# FredT232H_Board.net
KiCad netlist of a schematic drawn in EAGLE
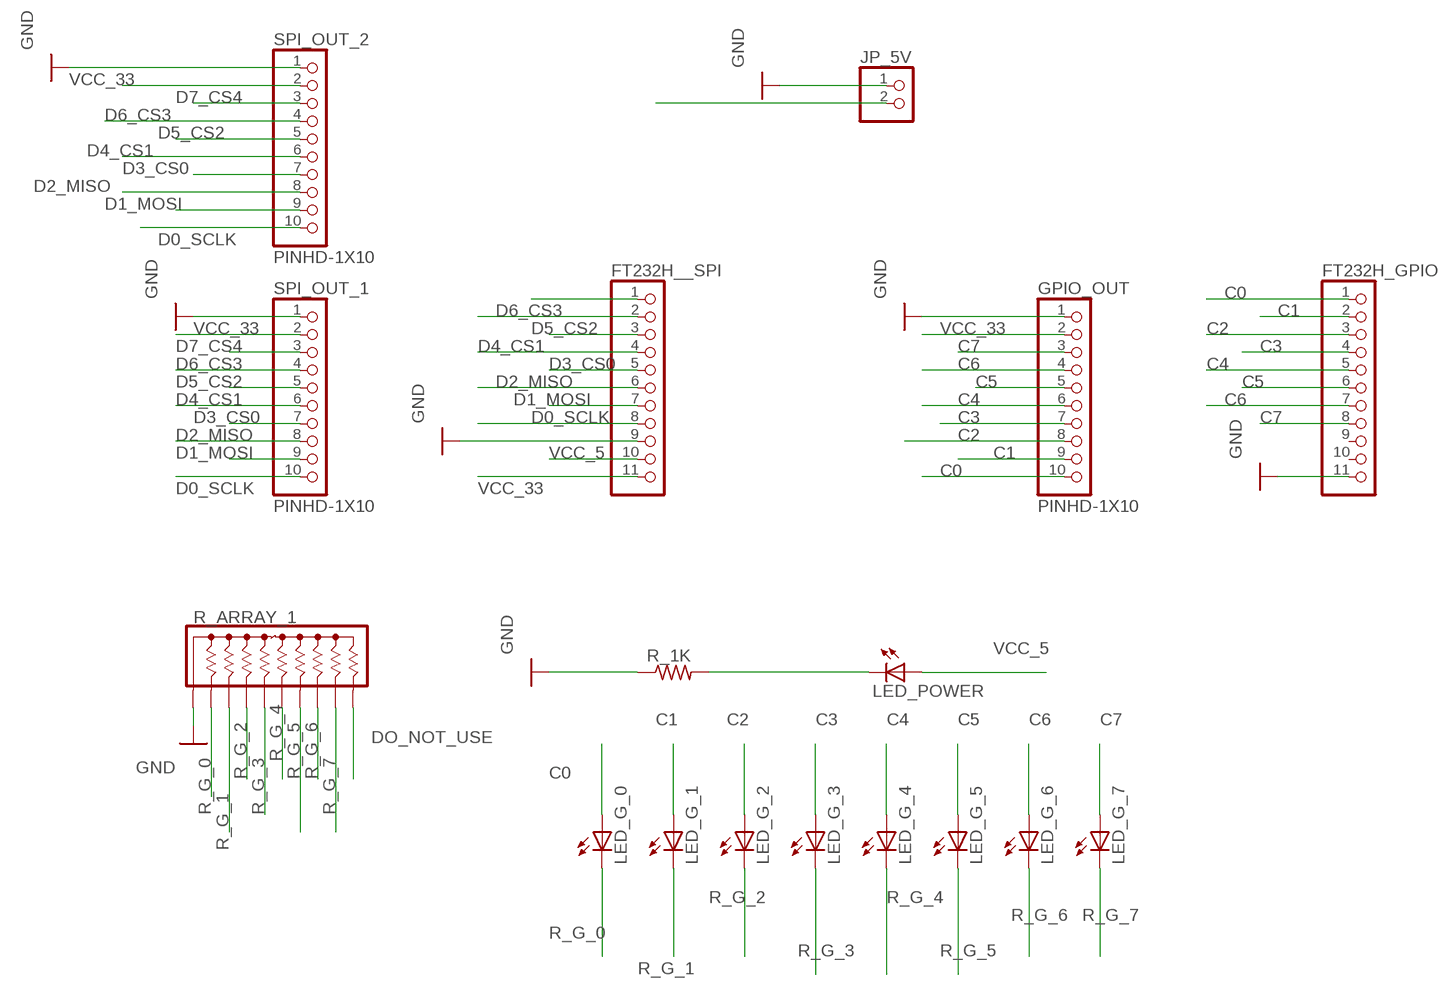
[diagram p0: schematic, sheet 1]

(export (version "E")
  (design (tool "Eeschema 10.0.6"))
  (components
    (comp (ref "FT232H_GPIO")
      (value "PINHD-1X11")
      (footprint "eagle-import:1X11")
      (libsource (lib "eagle-import") (part "PINHD-1X11"))
    )
    (comp (ref "FT232H__SPI")
      (value "PINHD-1X11")
      (footprint "eagle-import:1X11")
      (libsource (lib "eagle-import") (part "PINHD-1X11"))
    )
    (comp (ref "GPIO_OUT")
      (value "PINHD-1X10")
      (footprint "eagle-import:1X10-BIG")
      (libsource (lib "eagle-import") (part "PINHD-1X10"))
    )
    (comp (ref "JP_5V")
      (value "PINHD-1X2")
      (footprint "eagle-import:1X02")
      (libsource (lib "eagle-import") (part "PINHD-1X2"))
    )
    (comp (ref "LED_G_0")
      (value "LEDSMT1206")
      (footprint "eagle-import:1206")
      (libsource (lib "eagle-import") (part "LEDSMT1206"))
    )
    (comp (ref "LED_G_1")
      (value "LEDSMT1206")
      (footprint "eagle-import:1206")
      (libsource (lib "eagle-import") (part "LEDSMT1206"))
    )
    (comp (ref "LED_G_2")
      (value "LEDSMT1206")
      (footprint "eagle-import:1206")
      (libsource (lib "eagle-import") (part "LEDSMT1206"))
    )
    (comp (ref "LED_G_3")
      (value "LEDSMT1206")
      (footprint "eagle-import:1206")
      (libsource (lib "eagle-import") (part "LEDSMT1206"))
    )
    (comp (ref "LED_G_4")
      (value "LEDSMT1206")
      (footprint "eagle-import:1206")
      (libsource (lib "eagle-import") (part "LEDSMT1206"))
    )
    (comp (ref "LED_G_5")
      (value "LEDSMT1206")
      (footprint "eagle-import:1206")
      (libsource (lib "eagle-import") (part "LEDSMT1206"))
    )
    (comp (ref "LED_G_6")
      (value "LEDSMT1206")
      (footprint "eagle-import:1206")
      (libsource (lib "eagle-import") (part "LEDSMT1206"))
    )
    (comp (ref "LED_G_7")
      (value "LEDSMT1206")
      (footprint "eagle-import:1206")
      (libsource (lib "eagle-import") (part "LEDSMT1206"))
    )
    (comp (ref "LED_POWER")
      (value "LEDSMT1206")
      (footprint "eagle-import:1206")
      (libsource (lib "eagle-import") (part "LEDSMT1206"))
    )
    (comp (ref "R_1K")
      (value "R-US_R1206")
      (footprint "eagle-import:R1206")
      (libsource (lib "eagle-import") (part "R-US_R1206"))
    )
    (comp (ref "R_ARRAY_1")
      (value "4610X")
      (footprint "eagle-import:SIP10")
      (libsource (lib "eagle-import") (part "4610X"))
    )
    (comp (ref "SPI_OUT_1")
      (value "PINHD-1X10")
      (footprint "eagle-import:1X10-BIG")
      (libsource (lib "eagle-import") (part "PINHD-1X10"))
    )
    (comp (ref "SPI_OUT_2")
      (value "PINHD-1X10")
      (footprint "eagle-import:1X10-BIG")
      (libsource (lib "eagle-import") (part "PINHD-1X10"))
    )
  )
  (nets
    (net (code "1") (name "/C0") (class "Default")
      (node (ref "FT232H_GPIO") (pin "1") (pinfunction "1_1") (pintype "passive"))
      (node (ref "GPIO_OUT") (pin "10") (pinfunction "10_10") (pintype "passive"))
      (node (ref "LED_G_0") (pin "A") (pinfunction "A_A") (pintype "passive"))
    )
    (net (code "2") (name "/C1") (class "Default")
      (node (ref "FT232H_GPIO") (pin "2") (pinfunction "2_2") (pintype "passive"))
      (node (ref "GPIO_OUT") (pin "9") (pinfunction "9_9") (pintype "passive"))
      (node (ref "LED_G_1") (pin "A") (pinfunction "A_A") (pintype "passive"))
    )
    (net (code "3") (name "/C2") (class "Default")
      (node (ref "FT232H_GPIO") (pin "3") (pinfunction "3_3") (pintype "passive"))
      (node (ref "GPIO_OUT") (pin "8") (pinfunction "8_8") (pintype "passive"))
      (node (ref "LED_G_2") (pin "A") (pinfunction "A_A") (pintype "passive"))
    )
    (net (code "4") (name "/C3") (class "Default")
      (node (ref "FT232H_GPIO") (pin "4") (pinfunction "4_4") (pintype "passive"))
      (node (ref "GPIO_OUT") (pin "7") (pinfunction "7_7") (pintype "passive"))
      (node (ref "LED_G_3") (pin "A") (pinfunction "A_A") (pintype "passive"))
    )
    (net (code "5") (name "/C4") (class "Default")
      (node (ref "FT232H_GPIO") (pin "5") (pinfunction "5_5") (pintype "passive"))
      (node (ref "GPIO_OUT") (pin "6") (pinfunction "6_6") (pintype "passive"))
      (node (ref "LED_G_4") (pin "A") (pinfunction "A_A") (pintype "passive"))
    )
    (net (code "6") (name "/C5") (class "Default")
      (node (ref "FT232H_GPIO") (pin "6") (pinfunction "6_6") (pintype "passive"))
      (node (ref "GPIO_OUT") (pin "5") (pinfunction "5_5") (pintype "passive"))
      (node (ref "LED_G_5") (pin "A") (pinfunction "A_A") (pintype "passive"))
    )
    (net (code "7") (name "/C6") (class "Default")
      (node (ref "FT232H_GPIO") (pin "7") (pinfunction "7_7") (pintype "passive"))
      (node (ref "GPIO_OUT") (pin "4") (pinfunction "4_4") (pintype "passive"))
      (node (ref "LED_G_6") (pin "A") (pinfunction "A_A") (pintype "passive"))
    )
    (net (code "8") (name "/C7") (class "Default")
      (node (ref "FT232H_GPIO") (pin "8") (pinfunction "8_8") (pintype "passive"))
      (node (ref "GPIO_OUT") (pin "3") (pinfunction "3_3") (pintype "passive"))
      (node (ref "LED_G_7") (pin "A") (pinfunction "A_A") (pintype "passive"))
    )
    (net (code "9") (name "/D0_SCLK") (class "Default")
      (node (ref "FT232H__SPI") (pin "8") (pinfunction "8_8") (pintype "passive"))
      (node (ref "SPI_OUT_1") (pin "10") (pinfunction "10_10") (pintype "passive"))
      (node (ref "SPI_OUT_2") (pin "10") (pinfunction "10_10") (pintype "passive"))
    )
    (net (code "10") (name "/D1_MOSI") (class "Default")
      (node (ref "FT232H__SPI") (pin "7") (pinfunction "7_7") (pintype "passive"))
      (node (ref "SPI_OUT_1") (pin "9") (pinfunction "9_9") (pintype "passive"))
      (node (ref "SPI_OUT_2") (pin "9") (pinfunction "9_9") (pintype "passive"))
    )
    (net (code "11") (name "/D2_MISO") (class "Default")
      (node (ref "FT232H__SPI") (pin "6") (pinfunction "6_6") (pintype "passive"))
      (node (ref "SPI_OUT_1") (pin "8") (pinfunction "8_8") (pintype "passive"))
      (node (ref "SPI_OUT_2") (pin "8") (pinfunction "8_8") (pintype "passive"))
    )
    (net (code "12") (name "/D3_CS0") (class "Default")
      (node (ref "FT232H__SPI") (pin "5") (pinfunction "5_5") (pintype "passive"))
      (node (ref "SPI_OUT_1") (pin "7") (pinfunction "7_7") (pintype "passive"))
      (node (ref "SPI_OUT_2") (pin "7") (pinfunction "7_7") (pintype "passive"))
    )
    (net (code "13") (name "/D4_CS1") (class "Default")
      (node (ref "FT232H__SPI") (pin "4") (pinfunction "4_4") (pintype "passive"))
      (node (ref "SPI_OUT_1") (pin "6") (pinfunction "6_6") (pintype "passive"))
      (node (ref "SPI_OUT_2") (pin "6") (pinfunction "6_6") (pintype "passive"))
    )
    (net (code "14") (name "/D5_CS2") (class "Default")
      (node (ref "FT232H__SPI") (pin "3") (pinfunction "3_3") (pintype "passive"))
      (node (ref "SPI_OUT_1") (pin "5") (pinfunction "5_5") (pintype "passive"))
      (node (ref "SPI_OUT_2") (pin "5") (pinfunction "5_5") (pintype "passive"))
    )
    (net (code "15") (name "/D6_CS3") (class "Default")
      (node (ref "FT232H__SPI") (pin "2") (pinfunction "2_2") (pintype "passive"))
      (node (ref "SPI_OUT_1") (pin "4") (pinfunction "4_4") (pintype "passive"))
      (node (ref "SPI_OUT_2") (pin "4") (pinfunction "4_4") (pintype "passive"))
    )
    (net (code "16") (name "/D7_CS4") (class "Default")
      (node (ref "FT232H__SPI") (pin "1") (pinfunction "1_1") (pintype "passive"))
      (node (ref "SPI_OUT_1") (pin "3") (pinfunction "3_3") (pintype "passive"))
      (node (ref "SPI_OUT_2") (pin "3") (pinfunction "3_3") (pintype "passive"))
    )
    (net (code "17") (name "/DO_NOT_USE") (class "Default")
      (node (ref "R_ARRAY_1") (pin "10") (pinfunction "10_10") (pintype "passive"))
    )
    (net (code "18") (name "/R_G_0") (class "Default")
      (node (ref "LED_G_0") (pin "C") (pinfunction "C_C") (pintype "passive"))
      (node (ref "R_ARRAY_1") (pin "2") (pinfunction "2_2") (pintype "passive"))
    )
    (net (code "19") (name "/R_G_1") (class "Default")
      (node (ref "LED_G_1") (pin "C") (pinfunction "C_C") (pintype "passive"))
      (node (ref "R_ARRAY_1") (pin "3") (pinfunction "3_3") (pintype "passive"))
    )
    (net (code "20") (name "/R_G_2") (class "Default")
      (node (ref "LED_G_2") (pin "C") (pinfunction "C_C") (pintype "passive"))
      (node (ref "R_ARRAY_1") (pin "4") (pinfunction "4_4") (pintype "passive"))
    )
    (net (code "21") (name "/R_G_3") (class "Default")
      (node (ref "LED_G_3") (pin "C") (pinfunction "C_C") (pintype "passive"))
      (node (ref "R_ARRAY_1") (pin "5") (pinfunction "5_5") (pintype "passive"))
    )
    (net (code "22") (name "/R_G_4") (class "Default")
      (node (ref "LED_G_4") (pin "C") (pinfunction "C_C") (pintype "passive"))
      (node (ref "R_ARRAY_1") (pin "6") (pinfunction "6_6") (pintype "passive"))
    )
    (net (code "23") (name "/R_G_5") (class "Default")
      (node (ref "LED_G_5") (pin "C") (pinfunction "C_C") (pintype "passive"))
      (node (ref "R_ARRAY_1") (pin "7") (pinfunction "7_7") (pintype "passive"))
    )
    (net (code "24") (name "/R_G_6") (class "Default")
      (node (ref "LED_G_6") (pin "C") (pinfunction "C_C") (pintype "passive"))
      (node (ref "R_ARRAY_1") (pin "8") (pinfunction "8_8") (pintype "passive"))
    )
    (net (code "25") (name "/R_G_7") (class "Default")
      (node (ref "LED_G_7") (pin "C") (pinfunction "C_C") (pintype "passive"))
      (node (ref "R_ARRAY_1") (pin "9") (pinfunction "9_9") (pintype "passive"))
    )
    (net (code "26") (name "/VCC_5") (class "Default")
      (node (ref "FT232H__SPI") (pin "10") (pinfunction "10_10") (pintype "passive"))
      (node (ref "JP_5V") (pin "2") (pinfunction "2_2") (pintype "passive"))
      (node (ref "LED_POWER") (pin "A") (pinfunction "A_A") (pintype "passive"))
    )
    (net (code "27") (name "/VCC_33") (class "Default")
      (node (ref "FT232H__SPI") (pin "11") (pinfunction "11_11") (pintype "passive"))
      (node (ref "GPIO_OUT") (pin "2") (pinfunction "2_2") (pintype "passive"))
      (node (ref "SPI_OUT_1") (pin "2") (pinfunction "2_2") (pintype "passive"))
      (node (ref "SPI_OUT_2") (pin "2") (pinfunction "2_2") (pintype "passive"))
    )
    (net (code "28") (name "GND") (class "Default")
      (node (ref "FT232H_GPIO") (pin "11") (pinfunction "11_11") (pintype "passive"))
      (node (ref "FT232H__SPI") (pin "9") (pinfunction "9_9") (pintype "passive"))
      (node (ref "GPIO_OUT") (pin "1") (pinfunction "1_1") (pintype "passive"))
      (node (ref "JP_5V") (pin "1") (pinfunction "1_1") (pintype "passive"))
      (node (ref "R_1K") (pin "1") (pinfunction "1_1") (pintype "passive"))
      (node (ref "R_ARRAY_1") (pin "1") (pinfunction "1_1") (pintype "passive"))
      (node (ref "SPI_OUT_1") (pin "1") (pinfunction "1_1") (pintype "passive"))
      (node (ref "SPI_OUT_2") (pin "1") (pinfunction "1_1") (pintype "passive"))
    )
    (net (code "29") (name "Net-(LED_POWER-PadC)") (class "Default")
      (node (ref "LED_POWER") (pin "C") (pinfunction "C_C") (pintype "passive"))
      (node (ref "R_1K") (pin "2") (pinfunction "2_2") (pintype "passive"))
    )
    (net (code "30") (name "unconnected-(FT232H_GPIO-Pad9)") (class "Default")
      (node (ref "FT232H_GPIO") (pin "9") (pinfunction "9_9") (pintype "passive"))
    )
    (net (code "31") (name "unconnected-(FT232H_GPIO-Pad10)") (class "Default")
      (node (ref "FT232H_GPIO") (pin "10") (pinfunction "10_10") (pintype "passive"))
    )
  )
)
